# customESC_Test.net
KiCad netlist of a schematic drawn in EAGLE
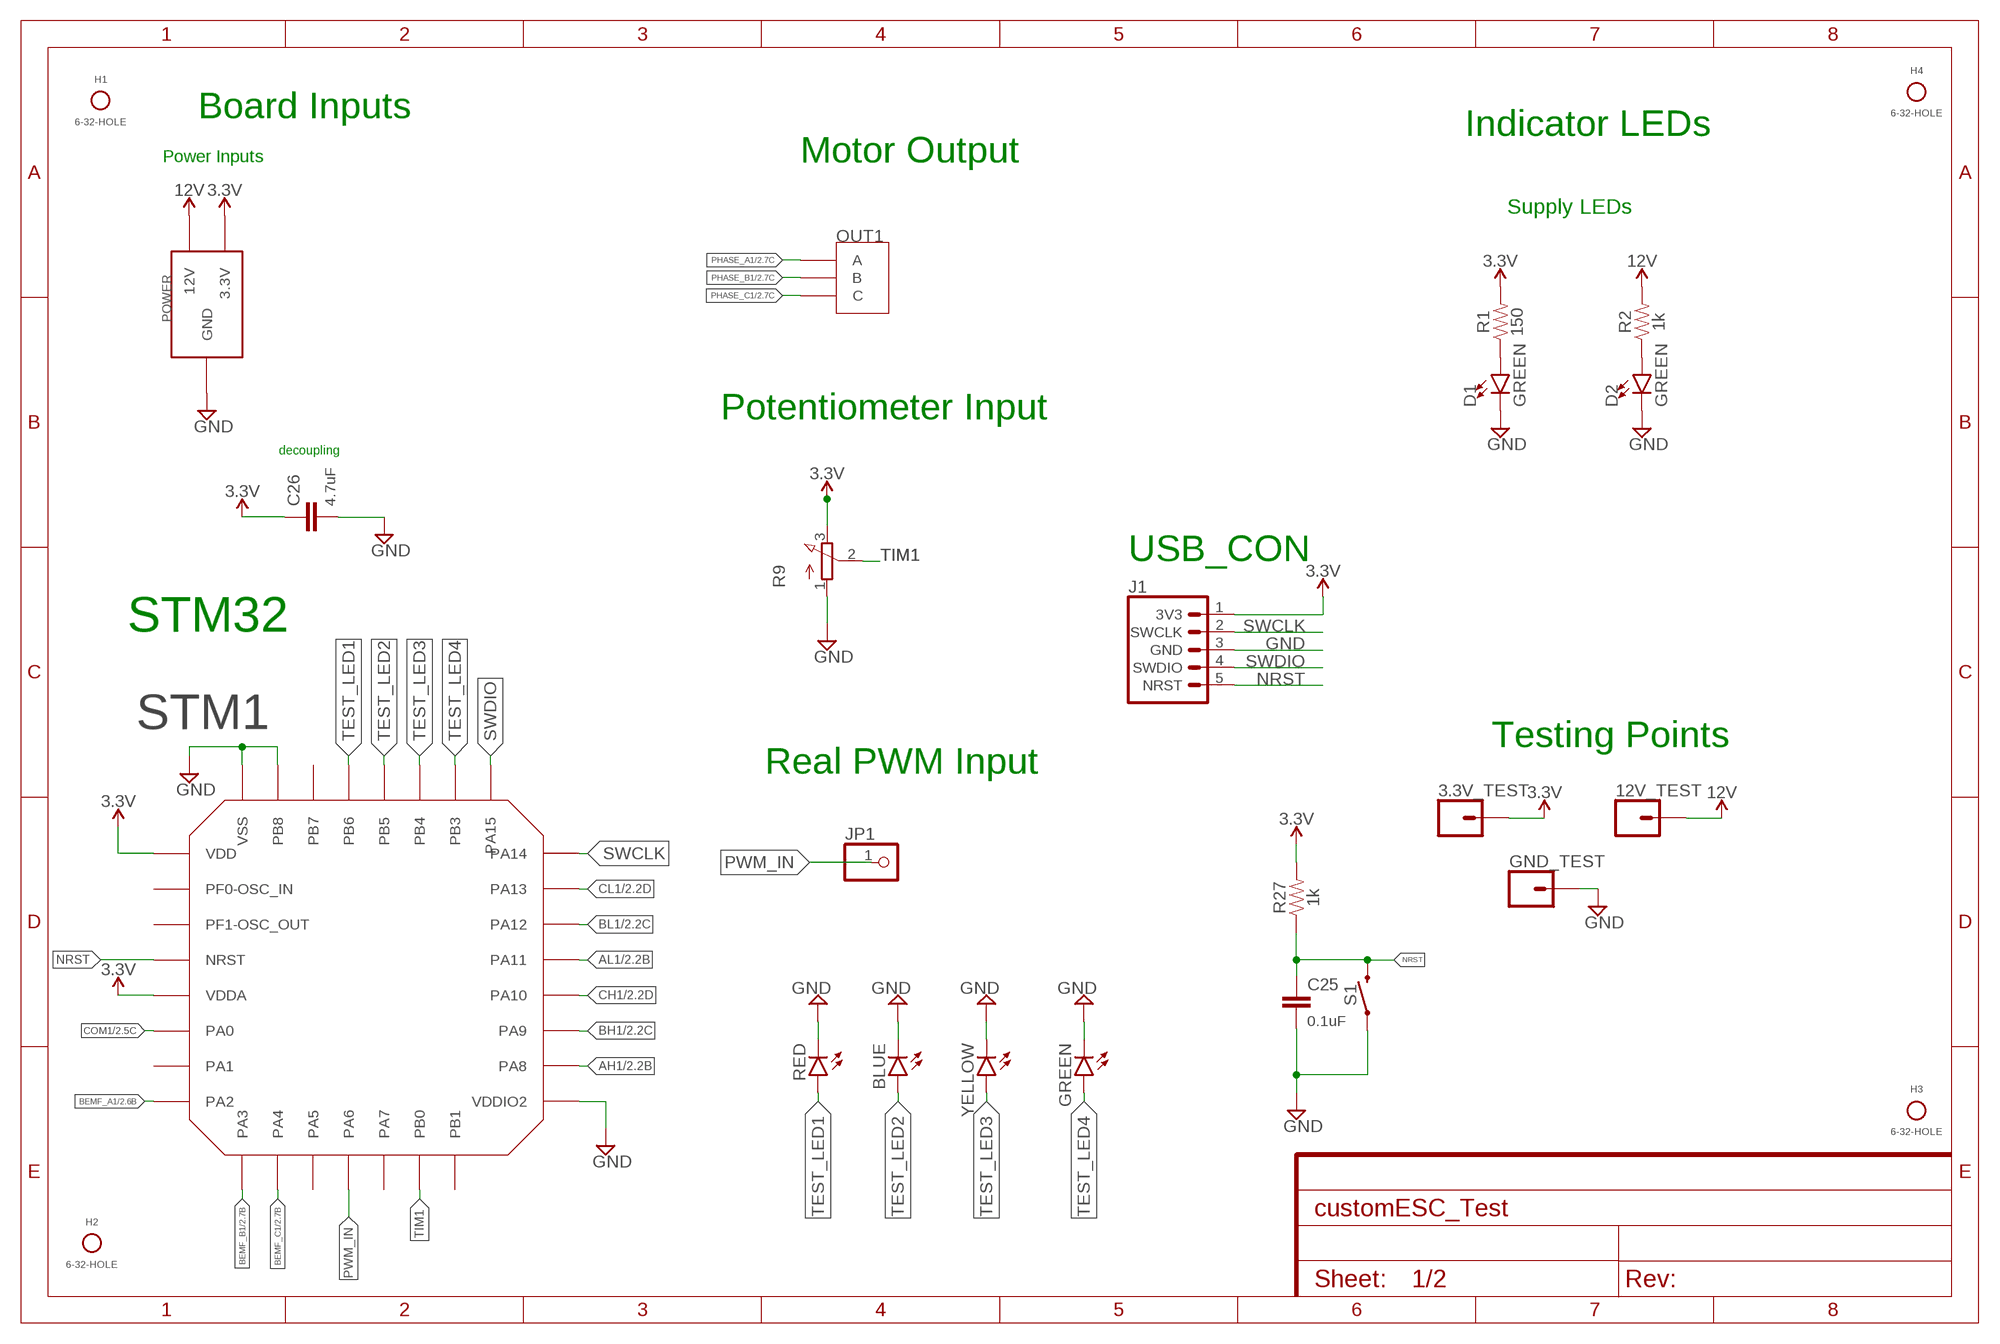
[diagram p0: schematic, sheet 1]
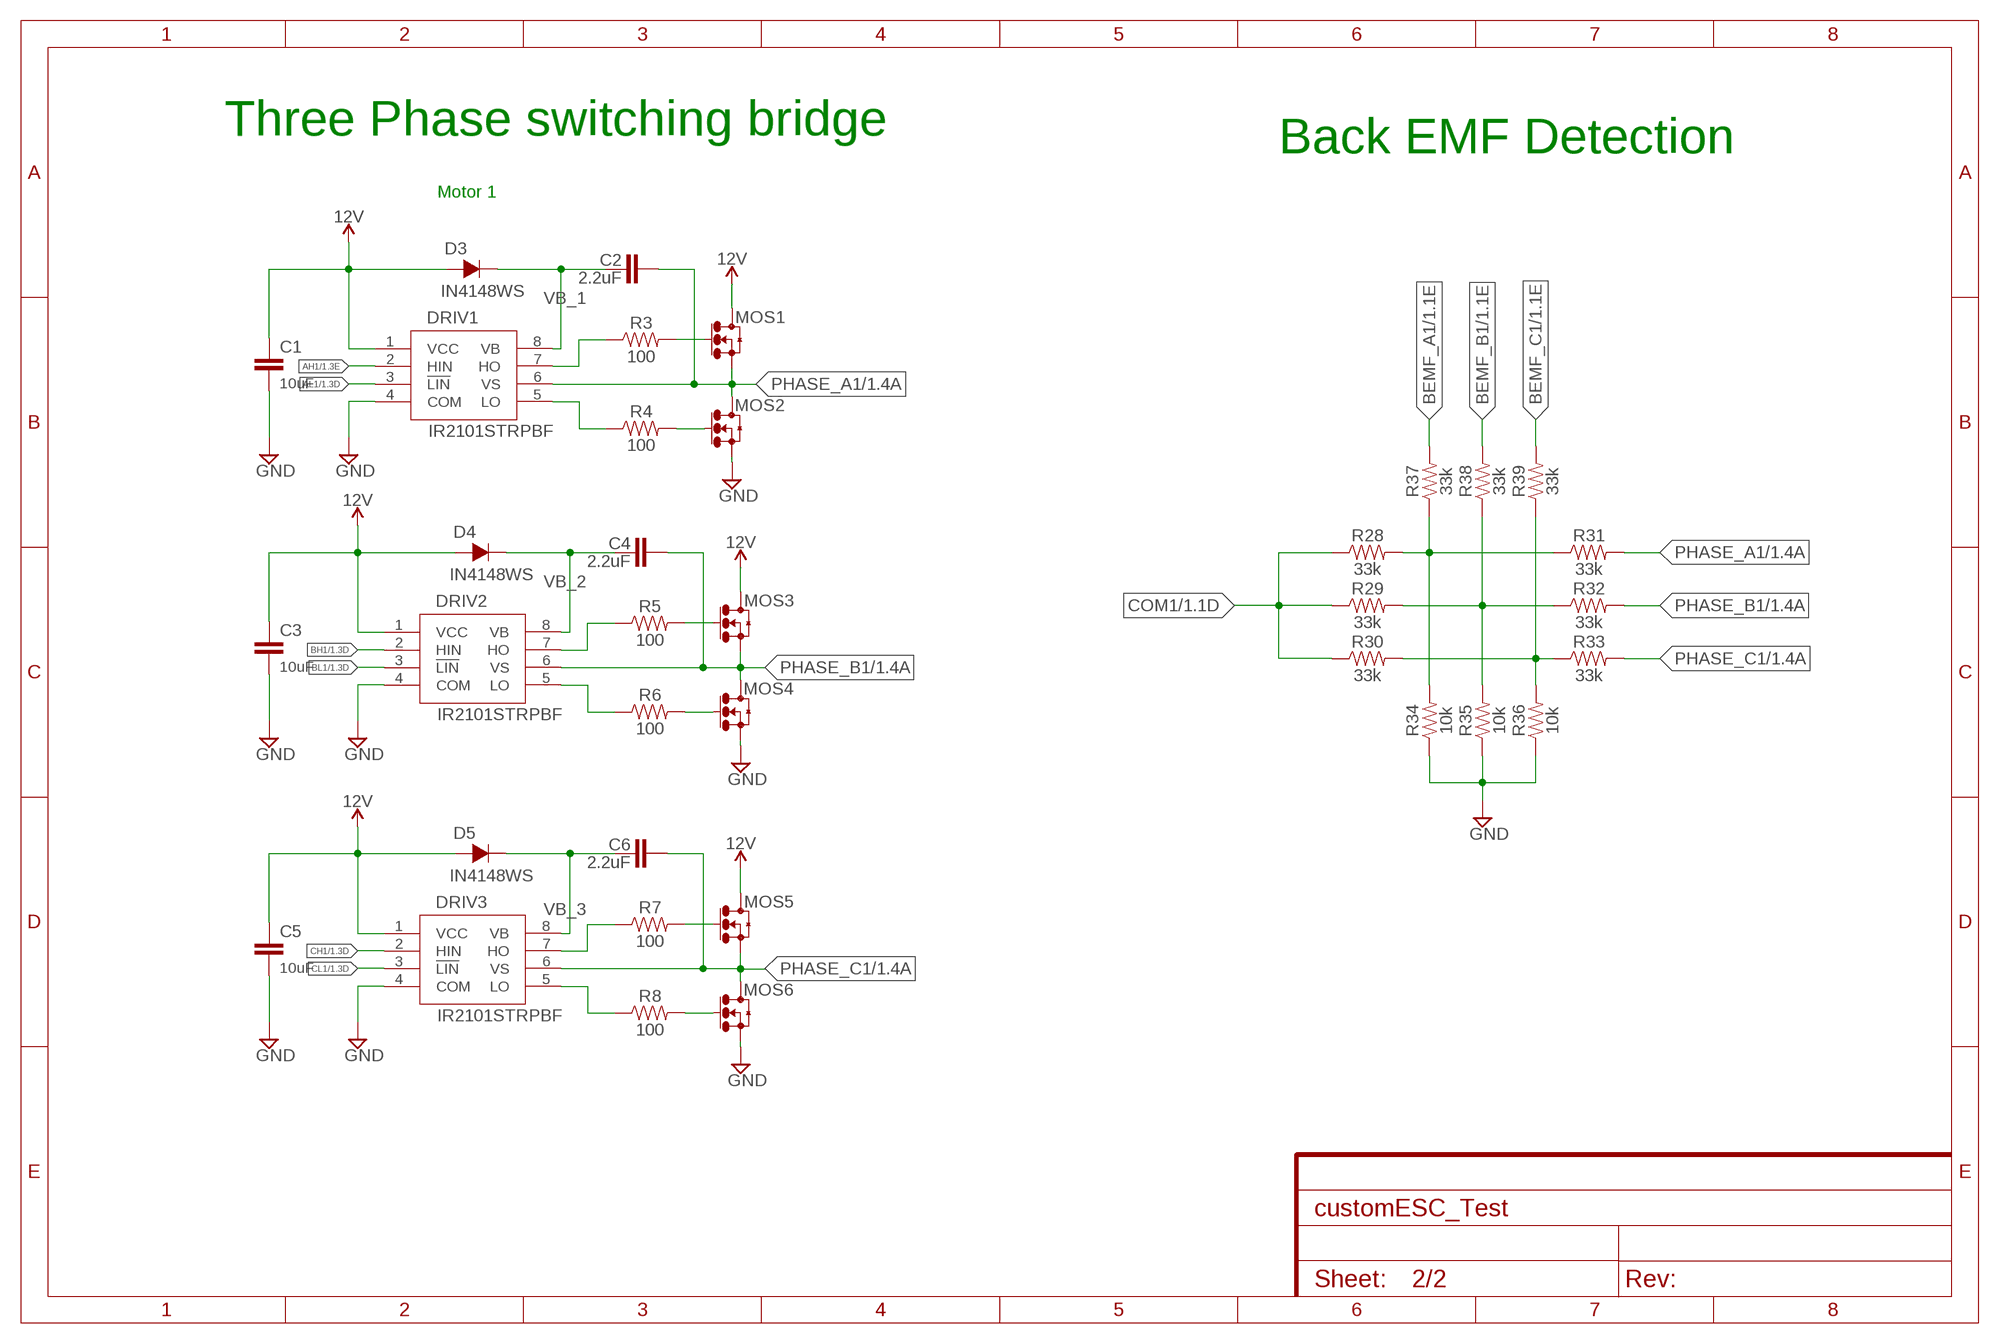
[diagram p1: schematic, sheet 2]

(export (version "E")
  (design (tool "Eeschema 10.0.6"))
  (components
    (comp (ref "3.3V_TEST")
      (value "CONN_01")
      (footprint "eagle-import:1X01")
      (libsource (lib "eagle-import") (part "CONN_01"))
    )
    (comp (ref "12V_TEST")
      (value "CONN_01")
      (footprint "eagle-import:1X01")
      (libsource (lib "eagle-import") (part "CONN_01"))
    )
    (comp (ref "BLUE")
      (value "LEDCHIPLED_0805")
      (footprint "eagle-import:CHIPLED_0805")
      (libsource (lib "eagle-import") (part "LEDCHIPLED_0805"))
    )
    (comp (ref "C25")
      (value "0.1uF")
      (footprint "eagle-import:0603")
      (libsource (lib "eagle-import") (part "10UF-0603-6.3V-20%"))
    )
    (comp (ref "C26")
      (value "4.7uF")
      (footprint "eagle-import:0603")
      (libsource (lib "eagle-import") (part "10UF-0603-6.3V-20%"))
    )
    (comp (ref "D1")
      (value "GREEN")
      (footprint "eagle-import:LED-0603")
      (libsource (lib "eagle-import") (part "LED-GREEN0603"))
    )
    (comp (ref "D2")
      (value "GREEN")
      (footprint "eagle-import:LED-0603")
      (libsource (lib "eagle-import") (part "LED-GREEN0603"))
    )
    (comp (ref "GND_TEST")
      (value "CONN_01")
      (footprint "eagle-import:1X01")
      (libsource (lib "eagle-import") (part "CONN_01"))
    )
    (comp (ref "GREEN")
      (value "LEDCHIPLED_0805")
      (footprint "eagle-import:CHIPLED_0805")
      (libsource (lib "eagle-import") (part "LEDCHIPLED_0805"))
    )
    (comp (ref "H1")
      (value "6-32-HOLE")
      (footprint "eagle-import:MOUNTING_HOLE")
      (libsource (lib "eagle-import") (part "6-32-HOLE"))
    )
    (comp (ref "H2")
      (value "6-32-HOLE")
      (footprint "eagle-import:MOUNTING_HOLE")
      (libsource (lib "eagle-import") (part "6-32-HOLE"))
    )
    (comp (ref "H3")
      (value "6-32-HOLE")
      (footprint "eagle-import:MOUNTING_HOLE")
      (libsource (lib "eagle-import") (part "6-32-HOLE"))
    )
    (comp (ref "H4")
      (value "6-32-HOLE")
      (footprint "eagle-import:MOUNTING_HOLE")
      (libsource (lib "eagle-import") (part "6-32-HOLE"))
    )
    (comp (ref "J1")
      (value "3V3 -SWCLK-GND-SWDIO- NRST")
      (footprint "eagle-import:1X05")
      (libsource (lib "eagle-import") (part "SWD_CONN"))
    )
    (comp (ref "JP1")
      (value "PINHD-1X1")
      (footprint "eagle-import:1X01")
      (libsource (lib "eagle-import") (part "PINHD-1X1"))
    )
    (comp (ref "OUT1")
      (value "IPBT-103-H1-T-S")
      (footprint "eagle-import:IPBT-103-H1-T-S")
      (libsource (lib "eagle-import") (part "IPBT-103-H1-T-S"))
    )
    (comp (ref "POWER")
      (value "12V-CONNECTOR")
      (footprint "eagle-import:12V-CONNECTOR")
      (libsource (lib "eagle-import") (part "12V-CONNECTOR"))
    )
    (comp (ref "R1")
      (value "150")
      (footprint "eagle-import:0603")
      (libsource (lib "eagle-import") (part "1KOHM-0603-1/10W-1%"))
    )
    (comp (ref "R2")
      (value "1k")
      (footprint "eagle-import:0603")
      (libsource (lib "eagle-import") (part "1KOHM-0603-1/10W-1%"))
    )
    (comp (ref "R9")
      (value "3RP/1610N")
      (footprint "eagle-import:3RP_1610N")
      (libsource (lib "eagle-import") (part "3RP/1610N"))
    )
    (comp (ref "R27")
      (value "1k")
      (footprint "eagle-import:0603")
      (libsource (lib "eagle-import") (part "1KOHM-0603-1/10W-1%"))
    )
    (comp (ref "RED")
      (value "LEDCHIPLED_0805")
      (footprint "eagle-import:CHIPLED_0805")
      (libsource (lib "eagle-import") (part "LEDCHIPLED_0805"))
    )
    (comp (ref "S1")
      (value "MOMENTARY-SWITCH-SPST-SMD-6.0X3.5MM")
      (footprint "eagle-import:TACTILE_SWITCH_SMD_6.0X3.5MM")
      (libsource (lib "eagle-import") (part "MOMENTARY-SWITCH-SPST-SMD-6.0X3.5MM"))
    )
    (comp (ref "STM1")
      (value "STM32F042K6T6")
      (footprint "eagle-import:STM32F042K6T6")
      (libsource (lib "eagle-import") (part "STM32F042K6T6"))
    )
    (comp (ref "YELLOW")
      (value "LEDCHIPLED_0805")
      (footprint "eagle-import:CHIPLED_0805")
      (libsource (lib "eagle-import") (part "LEDCHIPLED_0805"))
    )
    (comp (ref "C1")
      (value "10uF")
      (footprint "eagle-import:0603")
      (libsource (lib "eagle-import") (part "10UF-0603-6.3V-20%"))
    )
    (comp (ref "C2")
      (value "2.2uF")
      (footprint "eagle-import:0603")
      (libsource (lib "eagle-import") (part "10UF-0603-6.3V-20%"))
    )
    (comp (ref "C3")
      (value "10uF")
      (footprint "eagle-import:0603")
      (libsource (lib "eagle-import") (part "10UF-0603-6.3V-20%"))
    )
    (comp (ref "C4")
      (value "2.2uF")
      (footprint "eagle-import:0603")
      (libsource (lib "eagle-import") (part "10UF-0603-6.3V-20%"))
    )
    (comp (ref "C5")
      (value "10uF")
      (footprint "eagle-import:0603")
      (libsource (lib "eagle-import") (part "10UF-0603-6.3V-20%"))
    )
    (comp (ref "C6")
      (value "2.2uF")
      (footprint "eagle-import:0603")
      (libsource (lib "eagle-import") (part "10UF-0603-6.3V-20%"))
    )
    (comp (ref "D3")
      (value "IN4148WS")
      (footprint "eagle-import:IN4148WS")
      (libsource (lib "eagle-import") (part "IN4148WS"))
    )
    (comp (ref "D4")
      (value "IN4148WS")
      (footprint "eagle-import:IN4148WS")
      (libsource (lib "eagle-import") (part "IN4148WS"))
    )
    (comp (ref "D5")
      (value "IN4148WS")
      (footprint "eagle-import:IN4148WS")
      (libsource (lib "eagle-import") (part "IN4148WS"))
    )
    (comp (ref "DRIV1")
      (value "IR2101STRPBF")
      (footprint "eagle-import:IR2101STRPBF")
      (libsource (lib "eagle-import") (part "IR2101STRPBF"))
    )
    (comp (ref "DRIV2")
      (value "IR2101STRPBF")
      (footprint "eagle-import:IR2101STRPBF")
      (libsource (lib "eagle-import") (part "IR2101STRPBF"))
    )
    (comp (ref "DRIV3")
      (value "IR2101STRPBF")
      (footprint "eagle-import:IR2101STRPBF")
      (libsource (lib "eagle-import") (part "IR2101STRPBF"))
    )
    (comp (ref "MOS1")
      (value "IRLR7843TRPBF")
      (footprint "eagle-import:IRLR7843TRPBF")
      (libsource (lib "eagle-import") (part "IRLR7843TRPBF"))
    )
    (comp (ref "MOS2")
      (value "IRLR7843TRPBF")
      (footprint "eagle-import:IRLR7843TRPBF")
      (libsource (lib "eagle-import") (part "IRLR7843TRPBF"))
    )
    (comp (ref "MOS3")
      (value "IRLR7843TRPBF")
      (footprint "eagle-import:IRLR7843TRPBF")
      (libsource (lib "eagle-import") (part "IRLR7843TRPBF"))
    )
    (comp (ref "MOS4")
      (value "IRLR7843TRPBF")
      (footprint "eagle-import:IRLR7843TRPBF")
      (libsource (lib "eagle-import") (part "IRLR7843TRPBF"))
    )
    (comp (ref "MOS5")
      (value "IRLR7843TRPBF")
      (footprint "eagle-import:IRLR7843TRPBF")
      (libsource (lib "eagle-import") (part "IRLR7843TRPBF"))
    )
    (comp (ref "MOS6")
      (value "IRLR7843TRPBF")
      (footprint "eagle-import:IRLR7843TRPBF")
      (libsource (lib "eagle-import") (part "IRLR7843TRPBF"))
    )
    (comp (ref "R3")
      (value "100")
      (footprint "eagle-import:0603")
      (libsource (lib "eagle-import") (part "1KOHM-0603-1/10W-1%"))
    )
    (comp (ref "R4")
      (value "100")
      (footprint "eagle-import:0603")
      (libsource (lib "eagle-import") (part "1KOHM-0603-1/10W-1%"))
    )
    (comp (ref "R5")
      (value "100")
      (footprint "eagle-import:0603")
      (libsource (lib "eagle-import") (part "1KOHM-0603-1/10W-1%"))
    )
    (comp (ref "R6")
      (value "100")
      (footprint "eagle-import:0603")
      (libsource (lib "eagle-import") (part "1KOHM-0603-1/10W-1%"))
    )
    (comp (ref "R7")
      (value "100")
      (footprint "eagle-import:0603")
      (libsource (lib "eagle-import") (part "1KOHM-0603-1/10W-1%"))
    )
    (comp (ref "R8")
      (value "100")
      (footprint "eagle-import:0603")
      (libsource (lib "eagle-import") (part "1KOHM-0603-1/10W-1%"))
    )
    (comp (ref "R28")
      (value "33k")
      (footprint "eagle-import:0603")
      (libsource (lib "eagle-import") (part "1KOHM-0603-1/10W-1%"))
    )
    (comp (ref "R29")
      (value "33k")
      (footprint "eagle-import:0603")
      (libsource (lib "eagle-import") (part "1KOHM-0603-1/10W-1%"))
    )
    (comp (ref "R30")
      (value "33k")
      (footprint "eagle-import:0603")
      (libsource (lib "eagle-import") (part "1KOHM-0603-1/10W-1%"))
    )
    (comp (ref "R31")
      (value "33k")
      (footprint "eagle-import:0603")
      (libsource (lib "eagle-import") (part "1KOHM-0603-1/10W-1%"))
    )
    (comp (ref "R32")
      (value "33k")
      (footprint "eagle-import:0603")
      (libsource (lib "eagle-import") (part "1KOHM-0603-1/10W-1%"))
    )
    (comp (ref "R33")
      (value "33k")
      (footprint "eagle-import:0603")
      (libsource (lib "eagle-import") (part "1KOHM-0603-1/10W-1%"))
    )
    (comp (ref "R34")
      (value "10k")
      (footprint "eagle-import:0603")
      (libsource (lib "eagle-import") (part "1KOHM-0603-1/10W-1%"))
    )
    (comp (ref "R35")
      (value "10k")
      (footprint "eagle-import:0603")
      (libsource (lib "eagle-import") (part "1KOHM-0603-1/10W-1%"))
    )
    (comp (ref "R36")
      (value "10k")
      (footprint "eagle-import:0603")
      (libsource (lib "eagle-import") (part "1KOHM-0603-1/10W-1%"))
    )
    (comp (ref "R37")
      (value "33k")
      (footprint "eagle-import:0603")
      (libsource (lib "eagle-import") (part "1KOHM-0603-1/10W-1%"))
    )
    (comp (ref "R38")
      (value "33k")
      (footprint "eagle-import:0603")
      (libsource (lib "eagle-import") (part "1KOHM-0603-1/10W-1%"))
    )
    (comp (ref "R39")
      (value "33k")
      (footprint "eagle-import:0603")
      (libsource (lib "eagle-import") (part "1KOHM-0603-1/10W-1%"))
    )
  )
  (nets
    (net (code "1") (name "AH1") (class "Default")
      (node (ref "DRIV1") (pin "2") (pinfunction "HIN_2") (pintype "bidirectional"))
      (node (ref "STM1") (pin "PA8") (pinfunction "PA8_PA8") (pintype "bidirectional"))
    )
    (net (code "2") (name "AL1") (class "Default")
      (node (ref "DRIV1") (pin "3") (pinfunction "~{LIN}_3") (pintype "bidirectional"))
      (node (ref "STM1") (pin "PA11") (pinfunction "PA11_PA11") (pintype "bidirectional"))
    )
    (net (code "3") (name "BEMF_A1") (class "Default")
      (node (ref "R37") (pin "2") (pinfunction "2_2") (pintype "passive"))
      (node (ref "STM1") (pin "PA2") (pinfunction "PA2_PA2") (pintype "bidirectional"))
    )
    (net (code "4") (name "BEMF_B1") (class "Default")
      (node (ref "R38") (pin "2") (pinfunction "2_2") (pintype "passive"))
      (node (ref "STM1") (pin "PA3") (pinfunction "PA3_PA3") (pintype "bidirectional"))
    )
    (net (code "5") (name "BEMF_C1") (class "Default")
      (node (ref "R39") (pin "2") (pinfunction "2_2") (pintype "passive"))
      (node (ref "STM1") (pin "PA4") (pinfunction "PA4_PA4") (pintype "bidirectional"))
    )
    (net (code "6") (name "BH1") (class "Default")
      (node (ref "DRIV2") (pin "2") (pinfunction "HIN_2") (pintype "bidirectional"))
      (node (ref "STM1") (pin "PA9") (pinfunction "PA9_PA9") (pintype "bidirectional"))
    )
    (net (code "7") (name "BL1") (class "Default")
      (node (ref "DRIV2") (pin "3") (pinfunction "~{LIN}_3") (pintype "bidirectional"))
      (node (ref "STM1") (pin "PA12") (pinfunction "PA12_PA12") (pintype "bidirectional"))
    )
    (net (code "8") (name "CH1") (class "Default")
      (node (ref "DRIV3") (pin "2") (pinfunction "HIN_2") (pintype "bidirectional"))
      (node (ref "STM1") (pin "PA10") (pinfunction "PA10_PA10") (pintype "bidirectional"))
    )
    (net (code "9") (name "CL1") (class "Default")
      (node (ref "DRIV3") (pin "3") (pinfunction "~{LIN}_3") (pintype "bidirectional"))
      (node (ref "STM1") (pin "PA13") (pinfunction "PA13_PA13") (pintype "bidirectional"))
    )
    (net (code "10") (name "COM1") (class "Default")
      (node (ref "R28") (pin "1") (pinfunction "1_1") (pintype "passive"))
      (node (ref "R29") (pin "1") (pinfunction "1_1") (pintype "passive"))
      (node (ref "R30") (pin "1") (pinfunction "1_1") (pintype "passive"))
      (node (ref "STM1") (pin "PA0") (pinfunction "PA0_PA0") (pintype "bidirectional"))
    )
    (net (code "11") (name "GND") (class "Default")
      (node (ref "BLUE") (pin "C") (pinfunction "C_C") (pintype "passive"))
      (node (ref "C1") (pin "2") (pinfunction "2_2") (pintype "passive"))
      (node (ref "C25") (pin "2") (pinfunction "2_2") (pintype "passive"))
      (node (ref "C26") (pin "2") (pinfunction "2_2") (pintype "passive"))
      (node (ref "C3") (pin "2") (pinfunction "2_2") (pintype "passive"))
      (node (ref "C5") (pin "2") (pinfunction "2_2") (pintype "passive"))
      (node (ref "D1") (pin "C") (pinfunction "C_C") (pintype "passive"))
      (node (ref "D2") (pin "C") (pinfunction "C_C") (pintype "passive"))
      (node (ref "DRIV1") (pin "4") (pinfunction "COM_4") (pintype "bidirectional"))
      (node (ref "DRIV2") (pin "4") (pinfunction "COM_4") (pintype "bidirectional"))
      (node (ref "DRIV3") (pin "4") (pinfunction "COM_4") (pintype "bidirectional"))
      (node (ref "GND_TEST") (pin "1") (pinfunction "1_1") (pintype "passive"))
      (node (ref "GREEN") (pin "C") (pinfunction "C_C") (pintype "passive"))
      (node (ref "J1") (pin "3") (pinfunction "GND_3") (pintype "power_in"))
      (node (ref "MOS2") (pin "2") (pinfunction "DRAIN_2") (pintype "bidirectional"))
      (node (ref "MOS2") (pin "4") (pinfunction "DRAIN_4") (pintype "bidirectional"))
      (node (ref "MOS4") (pin "2") (pinfunction "DRAIN_2") (pintype "bidirectional"))
      (node (ref "MOS4") (pin "4") (pinfunction "DRAIN_4") (pintype "bidirectional"))
      (node (ref "MOS6") (pin "2") (pinfunction "DRAIN_2") (pintype "bidirectional"))
      (node (ref "MOS6") (pin "4") (pinfunction "DRAIN_4") (pintype "bidirectional"))
      (node (ref "POWER") (pin "GND") (pinfunction "GND_GND") (pintype "bidirectional"))
      (node (ref "POWER") (pin "GND@1") (pinfunction "GND_GND@1") (pintype "bidirectional"))
      (node (ref "POWER") (pin "GND@10") (pinfunction "GND_GND@10") (pintype "bidirectional"))
      (node (ref "POWER") (pin "GND@11") (pinfunction "GND_GND@11") (pintype "bidirectional"))
      (node (ref "POWER") (pin "GND@12") (pinfunction "GND_GND@12") (pintype "bidirectional"))
      (node (ref "POWER") (pin "GND@2") (pinfunction "GND_GND@2") (pintype "bidirectional"))
      (node (ref "POWER") (pin "GND@3") (pinfunction "GND_GND@3") (pintype "bidirectional"))
      (node (ref "POWER") (pin "GND@4") (pinfunction "GND_GND@4") (pintype "bidirectional"))
      (node (ref "POWER") (pin "GND@5") (pinfunction "GND_GND@5") (pintype "bidirectional"))
      (node (ref "POWER") (pin "GND@6") (pinfunction "GND_GND@6") (pintype "bidirectional"))
      (node (ref "POWER") (pin "GND@7") (pinfunction "GND_GND@7") (pintype "bidirectional"))
      (node (ref "POWER") (pin "GND@8") (pinfunction "GND_GND@8") (pintype "bidirectional"))
      (node (ref "POWER") (pin "GND@9") (pinfunction "GND_GND@9") (pintype "bidirectional"))
      (node (ref "R34") (pin "1") (pinfunction "1_1") (pintype "passive"))
      (node (ref "R35") (pin "1") (pinfunction "1_1") (pintype "passive"))
      (node (ref "R36") (pin "1") (pinfunction "1_1") (pintype "passive"))
      (node (ref "R9") (pin "1") (pinfunction "A_1") (pintype "passive"))
      (node (ref "RED") (pin "C") (pinfunction "C_C") (pintype "passive"))
      (node (ref "S1") (pin "1") (pinfunction "1_1") (pintype "passive"))
      (node (ref "STM1") (pin "PB8-BOOT0") (pinfunction "PB8_PB8-BOOT0") (pintype "bidirectional"))
      (node (ref "STM1") (pin "VDDIO2") (pinfunction "VDDIO2_VDDIO2") (pintype "bidirectional"))
      (node (ref "STM1") (pin "VSS") (pinfunction "VSS_VSS") (pintype "bidirectional"))
      (node (ref "STM1") (pin "VSS1") (pinfunction "VSS_VSS1") (pintype "bidirectional"))
      (node (ref "YELLOW") (pin "C") (pinfunction "C_C") (pintype "passive"))
    )
    (net (code "12") (name "NRST") (class "Default")
      (node (ref "C25") (pin "1") (pinfunction "1_1") (pintype "passive"))
      (node (ref "J1") (pin "5") (pinfunction "NRST_5") (pintype "open_collector"))
      (node (ref "R27") (pin "1") (pinfunction "1_1") (pintype "passive"))
      (node (ref "S1") (pin "2") (pinfunction "2_2") (pintype "passive"))
      (node (ref "STM1") (pin "NRST") (pinfunction "NRST_NRST") (pintype "bidirectional"))
    )
    (net (code "13") (name "Net-(D1-PadA)") (class "Default")
      (node (ref "D1") (pin "A") (pinfunction "A_A") (pintype "passive"))
      (node (ref "R1") (pin "1") (pinfunction "1_1") (pintype "passive"))
    )
    (net (code "14") (name "Net-(D2-PadA)") (class "Default")
      (node (ref "D2") (pin "A") (pinfunction "A_A") (pintype "passive"))
      (node (ref "R2") (pin "1") (pinfunction "1_1") (pintype "passive"))
    )
    (net (code "15") (name "Net-(DRIV1-HO)") (class "Default")
      (node (ref "DRIV1") (pin "7") (pinfunction "HO_7") (pintype "bidirectional"))
      (node (ref "R3") (pin "1") (pinfunction "1_1") (pintype "passive"))
    )
    (net (code "16") (name "Net-(DRIV1-LO)") (class "Default")
      (node (ref "DRIV1") (pin "5") (pinfunction "LO_5") (pintype "bidirectional"))
      (node (ref "R4") (pin "1") (pinfunction "1_1") (pintype "passive"))
    )
    (net (code "17") (name "Net-(DRIV2-HO)") (class "Default")
      (node (ref "DRIV2") (pin "7") (pinfunction "HO_7") (pintype "bidirectional"))
      (node (ref "R5") (pin "1") (pinfunction "1_1") (pintype "passive"))
    )
    (net (code "18") (name "Net-(DRIV2-LO)") (class "Default")
      (node (ref "DRIV2") (pin "5") (pinfunction "LO_5") (pintype "bidirectional"))
      (node (ref "R6") (pin "1") (pinfunction "1_1") (pintype "passive"))
    )
    (net (code "19") (name "Net-(DRIV3-HO)") (class "Default")
      (node (ref "DRIV3") (pin "7") (pinfunction "HO_7") (pintype "bidirectional"))
      (node (ref "R7") (pin "1") (pinfunction "1_1") (pintype "passive"))
    )
    (net (code "20") (name "Net-(DRIV3-LO)") (class "Default")
      (node (ref "DRIV3") (pin "5") (pinfunction "LO_5") (pintype "bidirectional"))
      (node (ref "R8") (pin "1") (pinfunction "1_1") (pintype "passive"))
    )
    (net (code "21") (name "Net-(MOS1-GATE)") (class "Default")
      (node (ref "MOS1") (pin "1") (pinfunction "GATE_1") (pintype "bidirectional"))
      (node (ref "R3") (pin "2") (pinfunction "2_2") (pintype "passive"))
    )
    (net (code "22") (name "Net-(MOS2-GATE)") (class "Default")
      (node (ref "MOS2") (pin "1") (pinfunction "GATE_1") (pintype "bidirectional"))
      (node (ref "R4") (pin "2") (pinfunction "2_2") (pintype "passive"))
    )
    (net (code "23") (name "Net-(MOS3-GATE)") (class "Default")
      (node (ref "MOS3") (pin "1") (pinfunction "GATE_1") (pintype "bidirectional"))
      (node (ref "R5") (pin "2") (pinfunction "2_2") (pintype "passive"))
    )
    (net (code "24") (name "Net-(MOS4-GATE)") (class "Default")
      (node (ref "MOS4") (pin "1") (pinfunction "GATE_1") (pintype "bidirectional"))
      (node (ref "R6") (pin "2") (pinfunction "2_2") (pintype "passive"))
    )
    (net (code "25") (name "Net-(MOS5-GATE)") (class "Default")
      (node (ref "MOS5") (pin "1") (pinfunction "GATE_1") (pintype "bidirectional"))
      (node (ref "R7") (pin "2") (pinfunction "2_2") (pintype "passive"))
    )
    (net (code "26") (name "Net-(MOS6-GATE)") (class "Default")
      (node (ref "MOS6") (pin "1") (pinfunction "GATE_1") (pintype "bidirectional"))
      (node (ref "R8") (pin "2") (pinfunction "2_2") (pintype "passive"))
    )
    (net (code "27") (name "Net-(R28-Pad2)") (class "Default")
      (node (ref "R28") (pin "2") (pinfunction "2_2") (pintype "passive"))
      (node (ref "R31") (pin "1") (pinfunction "1_1") (pintype "passive"))
      (node (ref "R34") (pin "2") (pinfunction "2_2") (pintype "passive"))
      (node (ref "R37") (pin "1") (pinfunction "1_1") (pintype "passive"))
    )
    (net (code "28") (name "Net-(R29-Pad2)") (class "Default")
      (node (ref "R29") (pin "2") (pinfunction "2_2") (pintype "passive"))
      (node (ref "R32") (pin "1") (pinfunction "1_1") (pintype "passive"))
      (node (ref "R35") (pin "2") (pinfunction "2_2") (pintype "passive"))
      (node (ref "R38") (pin "1") (pinfunction "1_1") (pintype "passive"))
    )
    (net (code "29") (name "Net-(R30-Pad2)") (class "Default")
      (node (ref "R30") (pin "2") (pinfunction "2_2") (pintype "passive"))
      (node (ref "R33") (pin "1") (pinfunction "1_1") (pintype "passive"))
      (node (ref "R36") (pin "2") (pinfunction "2_2") (pintype "passive"))
      (node (ref "R39") (pin "1") (pinfunction "1_1") (pintype "passive"))
    )
    (net (code "30") (name "PHASE_A1") (class "Default")
      (node (ref "C2") (pin "2") (pinfunction "2_2") (pintype "passive"))
      (node (ref "DRIV1") (pin "6") (pinfunction "VS_6") (pintype "bidirectional"))
      (node (ref "MOS1") (pin "2") (pinfunction "DRAIN_2") (pintype "bidirectional"))
      (node (ref "MOS1") (pin "4") (pinfunction "DRAIN_4") (pintype "bidirectional"))
      (node (ref "MOS2") (pin "3") (pinfunction "SOURCE_3") (pintype "bidirectional"))
      (node (ref "OUT1") (pin "1") (pinfunction "A_1") (pintype "bidirectional"))
      (node (ref "R31") (pin "2") (pinfunction "2_2") (pintype "passive"))
    )
    (net (code "31") (name "PHASE_B1") (class "Default")
      (node (ref "C4") (pin "2") (pinfunction "2_2") (pintype "passive"))
      (node (ref "DRIV2") (pin "6") (pinfunction "VS_6") (pintype "bidirectional"))
      (node (ref "MOS3") (pin "2") (pinfunction "DRAIN_2") (pintype "bidirectional"))
      (node (ref "MOS3") (pin "4") (pinfunction "DRAIN_4") (pintype "bidirectional"))
      (node (ref "MOS4") (pin "3") (pinfunction "SOURCE_3") (pintype "bidirectional"))
      (node (ref "OUT1") (pin "2") (pinfunction "B_2") (pintype "bidirectional"))
      (node (ref "R32") (pin "2") (pinfunction "2_2") (pintype "passive"))
    )
    (net (code "32") (name "PHASE_C1") (class "Default")
      (node (ref "C6") (pin "2") (pinfunction "2_2") (pintype "passive"))
      (node (ref "DRIV3") (pin "6") (pinfunction "VS_6") (pintype "bidirectional"))
      (node (ref "MOS5") (pin "2") (pinfunction "DRAIN_2") (pintype "bidirectional"))
      (node (ref "MOS5") (pin "4") (pinfunction "DRAIN_4") (pintype "bidirectional"))
      (node (ref "MOS6") (pin "3") (pinfunction "SOURCE_3") (pintype "bidirectional"))
      (node (ref "OUT1") (pin "3") (pinfunction "C_3") (pintype "bidirectional"))
      (node (ref "R33") (pin "2") (pinfunction "2_2") (pintype "passive"))
    )
    (net (code "33") (name "PWM_IN") (class "Default")
      (node (ref "JP1") (pin "1") (pinfunction "1_1") (pintype "passive"))
      (node (ref "STM1") (pin "PA6") (pinfunction "PA6_PA6") (pintype "bidirectional"))
    )
    (net (code "34") (name "SWCLK") (class "Default")
      (node (ref "J1") (pin "2") (pinfunction "SWCLK_2") (pintype "input"))
      (node (ref "STM1") (pin "PA14") (pinfunction "PA14_PA14") (pintype "bidirectional"))
    )
    (net (code "35") (name "SWDIO") (class "Default")
      (node (ref "J1") (pin "4") (pinfunction "SWDIO_4") (pintype "bidirectional"))
      (node (ref "STM1") (pin "PA15") (pinfunction "PA15_PA15") (pintype "bidirectional"))
    )
    (net (code "36") (name "TEST_LED1") (class "Default")
      (node (ref "RED") (pin "A") (pinfunction "A_A") (pintype "passive"))
      (node (ref "STM1") (pin "PB6") (pinfunction "PB6_PB6") (pintype "bidirectional"))
    )
    (net (code "37") (name "TEST_LED2") (class "Default")
      (node (ref "BLUE") (pin "A") (pinfunction "A_A") (pintype "passive"))
      (node (ref "STM1") (pin "PB5") (pinfunction "PB5_PB5") (pintype "bidirectional"))
    )
    (net (code "38") (name "TEST_LED3") (class "Default")
      (node (ref "STM1") (pin "PB4") (pinfunction "PB4_PB4") (pintype "bidirectional"))
      (node (ref "YELLOW") (pin "A") (pinfunction "A_A") (pintype "passive"))
    )
    (net (code "39") (name "TEST_LED4") (class "Default")
      (node (ref "GREEN") (pin "A") (pinfunction "A_A") (pintype "passive"))
      (node (ref "STM1") (pin "PB3") (pinfunction "PB3_PB3") (pintype "bidirectional"))
    )
    (net (code "40") (name "TIM1") (class "Default")
      (node (ref "R9") (pin "2") (pinfunction "S_2") (pintype "passive"))
      (node (ref "STM1") (pin "PB0") (pinfunction "PB0_PB0") (pintype "bidirectional"))
    )
    (net (code "41") (name "VB_1") (class "Default")
      (node (ref "C2") (pin "1") (pinfunction "1_1") (pintype "passive"))
      (node (ref "D3") (pin "P$2") (pinfunction "P$2_P$2") (pintype "bidirectional"))
      (node (ref "DRIV1") (pin "8") (pinfunction "VB_8") (pintype "bidirectional"))
    )
    (net (code "42") (name "VB_2") (class "Default")
      (node (ref "C4") (pin "1") (pinfunction "1_1") (pintype "passive"))
      (node (ref "D4") (pin "P$2") (pinfunction "P$2_P$2") (pintype "bidirectional"))
      (node (ref "DRIV2") (pin "8") (pinfunction "VB_8") (pintype "bidirectional"))
    )
    (net (code "43") (name "VB_3") (class "Default")
      (node (ref "C6") (pin "1") (pinfunction "1_1") (pintype "passive"))
      (node (ref "D5") (pin "P$2") (pinfunction "P$2_P$2") (pintype "bidirectional"))
      (node (ref "DRIV3") (pin "8") (pinfunction "VB_8") (pintype "bidirectional"))
    )
    (net (code "44") (name "VCC_1") (class "Default")
      (node (ref "3.3V_TEST") (pin "1") (pinfunction "1_1") (pintype "passive"))
      (node (ref "C26") (pin "1") (pinfunction "1_1") (pintype "passive"))
      (node (ref "J1") (pin "1") (pinfunction "3V3_1") (pintype "power_in"))
      (node (ref "POWER") (pin "3.3V") (pinfunction "3.3V_3.3V") (pintype "bidirectional"))
      (node (ref "R1") (pin "2") (pinfunction "2_2") (pintype "passive"))
      (node (ref "R27") (pin "2") (pinfunction "2_2") (pintype "passive"))
      (node (ref "R9") (pin "3") (pinfunction "E_3") (pintype "passive"))
      (node (ref "STM1") (pin "VDD") (pinfunction "VDD_VDD") (pintype "bidirectional"))
      (node (ref "STM1") (pin "VDDA") (pinfunction "VDDA_VDDA") (pintype "bidirectional"))
    )
    (net (code "45") (name "VCC_2") (class "Default")
      (node (ref "12V_TEST") (pin "1") (pinfunction "1_1") (pintype "passive"))
      (node (ref "C1") (pin "1") (pinfunction "1_1") (pintype "passive"))
      (node (ref "C3") (pin "1") (pinfunction "1_1") (pintype "passive"))
      (node (ref "C5") (pin "1") (pinfunction "1_1") (pintype "passive"))
      (node (ref "D3") (pin "P$1") (pinfunction "P$1_P$1") (pintype "bidirectional"))
      (node (ref "D4") (pin "P$1") (pinfunction "P$1_P$1") (pintype "bidirectional"))
      (node (ref "D5") (pin "P$1") (pinfunction "P$1_P$1") (pintype "bidirectional"))
      (node (ref "DRIV1") (pin "1") (pinfunction "VCC_1") (pintype "bidirectional"))
      (node (ref "DRIV2") (pin "1") (pinfunction "VCC_1") (pintype "bidirectional"))
      (node (ref "DRIV3") (pin "1") (pinfunction "VCC_1") (pintype "bidirectional"))
      (node (ref "MOS1") (pin "3") (pinfunction "SOURCE_3") (pintype "bidirectional"))
      (node (ref "MOS3") (pin "3") (pinfunction "SOURCE_3") (pintype "bidirectional"))
      (node (ref "MOS5") (pin "3") (pinfunction "SOURCE_3") (pintype "bidirectional"))
      (node (ref "POWER") (pin "12V@1") (pinfunction "12V_12V@1") (pintype "bidirectional"))
      (node (ref "POWER") (pin "12V@10") (pinfunction "12V_12V@10") (pintype "bidirectional"))
      (node (ref "POWER") (pin "12V@11") (pinfunction "12V_12V@11") (pintype "bidirectional"))
      (node (ref "POWER") (pin "12V@12") (pinfunction "12V_12V@12") (pintype "bidirectional"))
      (node (ref "POWER") (pin "12V@2") (pinfunction "12V_12V@2") (pintype "bidirectional"))
      (node (ref "POWER") (pin "12V@3") (pinfunction "12V_12V@3") (pintype "bidirectional"))
      (node (ref "POWER") (pin "12V@4") (pinfunction "12V_12V@4") (pintype "bidirectional"))
      (node (ref "POWER") (pin "12V@5") (pinfunction "12V_12V@5") (pintype "bidirectional"))
      (node (ref "POWER") (pin "12V@6") (pinfunction "12V_12V@6") (pintype "bidirectional"))
      (node (ref "POWER") (pin "12V@7") (pinfunction "12V_12V@7") (pintype "bidirectional"))
      (node (ref "POWER") (pin "12V@8") (pinfunction "12V_12V@8") (pintype "bidirectional"))
      (node (ref "POWER") (pin "12V@9") (pinfunction "12V_12V@9") (pintype "bidirectional"))
      (node (ref "R2") (pin "2") (pinfunction "2_2") (pintype "passive"))
    )
    (net (code "46") (name "unconnected-(STM1-PadPA1)") (class "Default")
      (node (ref "STM1") (pin "PA1") (pinfunction "PA1_PA1") (pintype "bidirectional"))
    )
    (net (code "47") (name "unconnected-(STM1-PadPA5)") (class "Default")
      (node (ref "STM1") (pin "PA5") (pinfunction "PA5_PA5") (pintype "bidirectional"))
    )
    (net (code "48") (name "unconnected-(STM1-PadPA7)") (class "Default")
      (node (ref "STM1") (pin "PA7") (pinfunction "PA7_PA7") (pintype "bidirectional"))
    )
    (net (code "49") (name "unconnected-(STM1-PadPB1)") (class "Default")
      (node (ref "STM1") (pin "PB1") (pinfunction "PB1_PB1") (pintype "bidirectional"))
    )
    (net (code "50") (name "unconnected-(STM1-PadPB7)") (class "Default")
      (node (ref "STM1") (pin "PB7") (pinfunction "PB7_PB7") (pintype "bidirectional"))
    )
    (net (code "51") (name "unconnected-(STM1-PadPF0-OSC_IN)") (class "Default")
      (node (ref "STM1") (pin "PF0-OSC_IN") (pinfunction "PF0-OSC_IN_PF0-OSC_IN") (pintype "bidirectional"))
    )
    (net (code "52") (name "unconnected-(STM1-PadPF1-OSC_OUT)") (class "Default")
      (node (ref "STM1") (pin "PF1-OSC_OUT") (pinfunction "PF1-OSC_OUT_PF1-OSC_OUT") (pintype "bidirectional"))
    )
  )
)
